# Connector-Section.net
KiCad netlist of a schematic drawn in Altium Designer
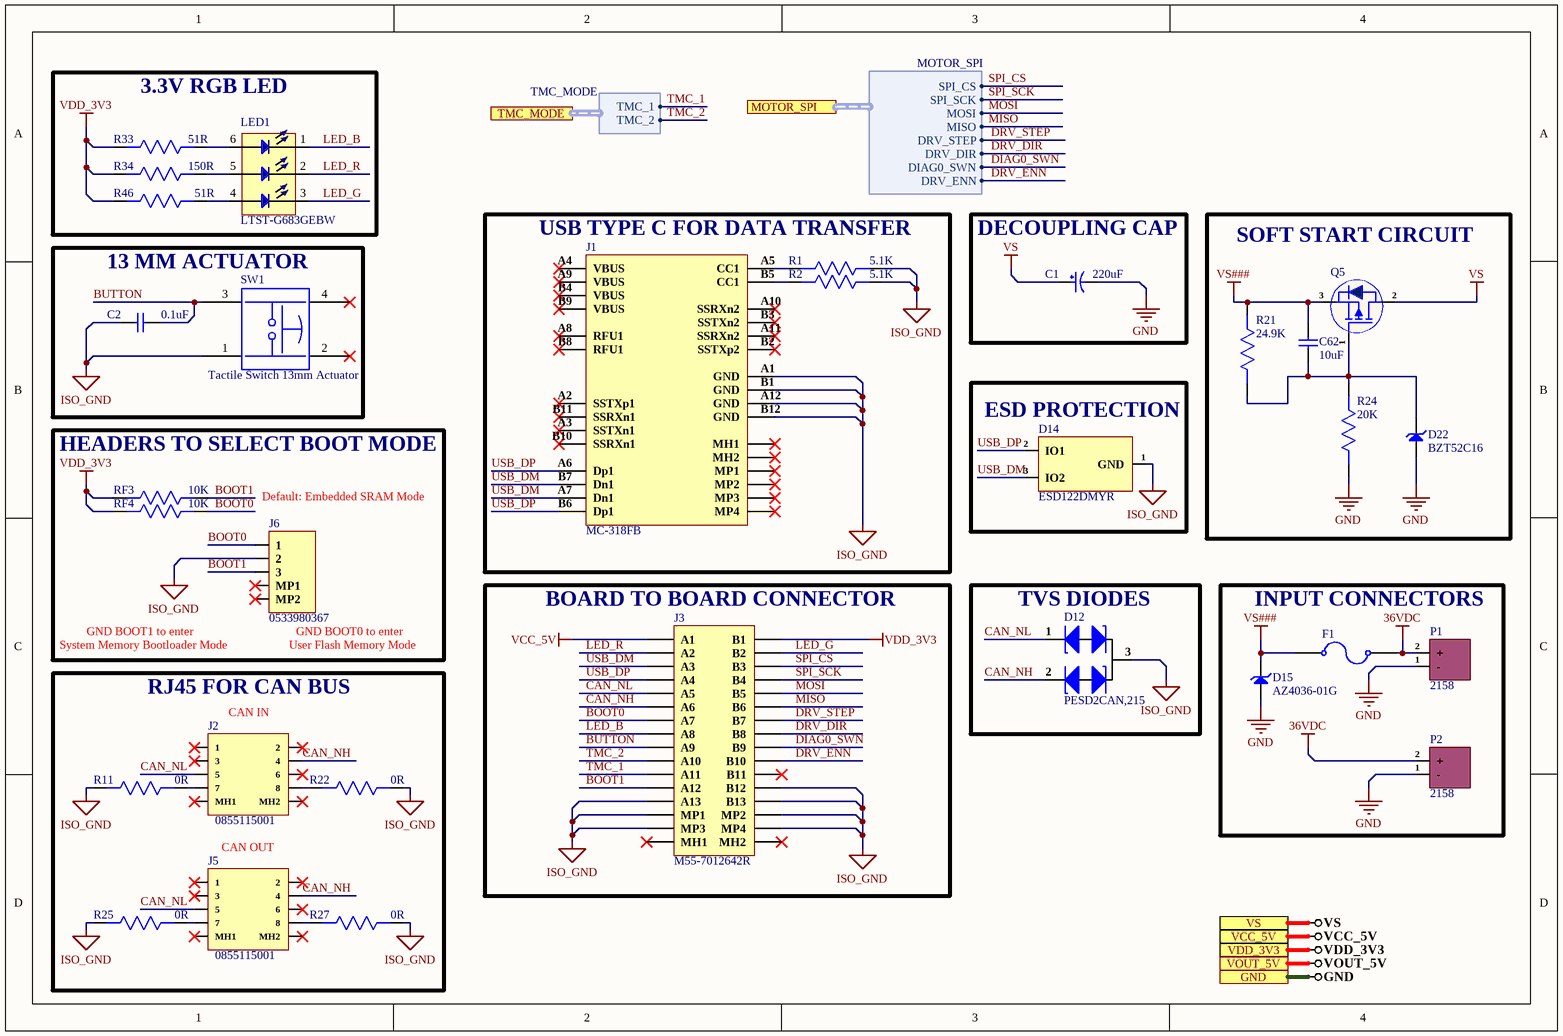
[diagram p0: Connector-Section.SchDoc]

(export (version "E")
  (design (tool "Eeschema 10.0.6"))
  (components
    (comp (ref "C1")
      (value "220uF")
      (footprint "EEEFT1H221AP")
      (description "CAP ALUM 220UF 20% 50V SMD")
      (fields
        (field (name "MANUFACTURER") "Panasonic")
        (field (name "MANUFACTURER PART NUMBER") "EEEFT1H221AP")
      )
      (libsource (lib "eSpark_centralized_Library(2022)") (part "EEEFT1H221AP"))
    )
    (comp (ref "C2")
      (value "0.1uF")
      (footprint "Cap 0603")
      (description "Cap Ceramic 0.1uF 50VDC X7R 10% SMD 0603 Paper T/R")
      (fields
        (field (name "MANUFACTURER") "Samsung")
        (field (name "MANUFACTURER PART NUMBER") "CL10B104KB8NNNC")
      )
      (libsource (lib "Cole_Benson") (part "CL10B104KB8NNNC"))
    )
    (comp (ref "C62")
      (value "10uF")
      (footprint "Cap0805")
      (description "CAP CER 10UF 50V X5R 0805")
      (fields
        (field (name "MANUFACTURER") "Samsung")
        (field (name "MANUFACTURER PART NUMBER") "CL21A106KBYQNNE")
      )
      (libsource (lib "Cole_Benson") (part "CL21A106KBYQNNE"))
    )
    (comp (ref "D12")
      (value "PESD2CAN,215")
      (footprint "SOT-23")
      (description "TVS DIODE 24VWM 41VC TO236AB")
      (fields (field (name "MANUFACTURER") "Nexperia"))
      (libsource (lib "Cole_Benson") (part "PESD2CAN,215"))
    )
    (comp (ref "D14")
      (value "ESD122DMYR")
      (footprint "X2-SON-3(0.6x1.3)")
      (description "TVS DIODE 3.6VWM 8.4VC 3X2SON")
      (fields (field (name "MANUFACTURER") "Texas Instruments") (field (name "LCSC PART NUMBER") "C1975871"))
      (libsource (lib "Cole_Benson") (part "ESD122DMYR"))
    )
    (comp (ref "D15")
      (value "AZ4036-01G")
      (footprint "SOD-123")
      (description "TVS DEVICE HIGH VOLTAGE 1-CH 36V")
      (fields (field (name "MANUFACTURER") "Amazing"))
      (libsource (lib "Cole_Benson") (part "AZ4036-01G"))
    )
    (comp (ref "D22")
      (value "BZT52C16")
      (footprint "SOD-123")
      (description "±5% Single 15.3V~17.1V 500mW 16V SOD-123 Zener Diodes ROHS")
      (fields (field (name "MANUFACTURER") "Shikues") (field (name "LCSC PART NUMBER") "C216724"))
      (libsource (lib "Cole_Benson") (part "BZT52C16"))
    )
    (comp (ref "F1")
      (value "0685P9100-01")
      (footprint "Fuse 1206 (3216 Metric)")
      (description "FUSE BOARD MOUNT 10A 50VDC 1206")
      (fields (field (name "MANUFACTURER") "Bel"))
      (libsource (lib "Cole_Benson") (part "0685P9100-01"))
    )
    (comp (ref "J1")
      (value "MC-318FB")
      (footprint "MC-318FB")
      (description "USB 3.0 3A 1 Brick nogging 24 Female -35℃~+75℃ Type-C SMD USB Connectors ROHS")
      (fields (field (name "MANUFACTURER") "SOFNG"))
      (libsource (lib "Cole_Benson") (part "MC-318FB"))
    )
    (comp (ref "J2")
      (value "0855115001")
      (footprint "0855115001")
      (description "CONN MOD JACK 8P8C VERT UNSHLD")
      (fields (field (name "MANUFACTURER") "Molex") (field (name "MANUFACTURER PART NUMBER") "85511-5001"))
      (libsource (lib "eSpark_centralized_Library(2022)") (part "0855115001"))
    )
    (comp (ref "J3")
      (value "M55-7012642R")
      (footprint "M55-7012642R")
      (description "CONN HEADER SMD 26POS 1.27MM")
      (fields (field (name "MANUFACTURER") "Harwin"))
      (libsource (lib "Cole_Benson") (part "M55-7012642R"))
    )
    (comp (ref "J5")
      (value "0855115001")
      (footprint "0855115001")
      (description "CONN MOD JACK 8P8C VERT UNSHLD")
      (fields (field (name "MANUFACTURER") "Molex") (field (name "MANUFACTURER PART NUMBER") "85511-5001"))
      (libsource (lib "eSpark_centralized_Library(2022)") (part "0855115001"))
    )
    (comp (ref "J6")
      (value "0533980367")
      (footprint "0533980367")
      (description "CONN HEADER SMD 3POS 1.25MM")
      (fields (field (name "MANUFACTURER") "Molex"))
      (libsource (lib "Cole_Benson") (part "0533980367"))
    )
    (comp (ref "LED1")
      (value "LTST-G683GEBW")
      (footprint "LTST-G683GEBW")
      (description "Standard LEDs - SMD SMD LED Red/Grn/Blue 625/1550/260 mcd")
      (fields (field (name "MANUFACTURER") "Vishay Lite-On"))
      (libsource (lib "Cole_Benson") (part "LTST-G683GEBW"))
    )
    (comp (ref "P1")
      (value "2158")
      (footprint "2158")
      (description "XT60 Connector Male-Female Pair, Black (Pololu)")
      (fields (field (name "MANUFACTURER") "Polulo"))
      (libsource (lib "Cole_Benson") (part "2158"))
    )
    (comp (ref "P2")
      (value "2158")
      (footprint "2158")
      (description "XT60 Connector Male-Female Pair, Black (Pololu)")
      (fields (field (name "MANUFACTURER") "Polulo"))
      (libsource (lib "Cole_Benson") (part "2158"))
    )
    (comp (ref "Q5")
      (value "SQD19P06-60L_GE3")
      (footprint "DPAK")
      (description "MOSFET P-CH 60V 20A TO252")
      (fields (field (name "MANUFACTURER") "Vishay") (field (name "LCSC PART NUMBER") "C143665"))
      (libsource (lib "Cole_Benson") (part "SQD19P06-60L_GE3"))
    )
    (comp (ref "R1")
      (value "5.1K")
      (footprint "Res0603")
      (description "RES SMD 5.1K OHM 5% 1/10W 0603")
      (fields
        (field (name "MANUFACTURER") "Yageo")
        (field (name "MANUFACTURER PART NUMBER") "RC0603JR-075K1L")
      )
      (libsource (lib "Cole_Benson") (part "RC0603JR-075K1L"))
    )
    (comp (ref "R2")
      (value "5.1K")
      (footprint "Res0603")
      (description "RES SMD 5.1K OHM 5% 1/10W 0603")
      (fields
        (field (name "MANUFACTURER") "Yageo")
        (field (name "MANUFACTURER PART NUMBER") "RC0603JR-075K1L")
      )
      (libsource (lib "Cole_Benson") (part "RC0603JR-075K1L"))
    )
    (comp (ref "R11")
      (value "0R")
      (footprint "Res0603")
      (description "RES SMD 0R, 1%, 0.1W, 0603")
      (fields
        (field (name "MANUFACTURER") "Yageo")
        (field (name "MANUFACTURER PART NUMBER") "RC0603FR-070RL")
      )
      (libsource (lib "Cole_Benson") (part "RC0603FR-070RL"))
    )
    (comp (ref "R21")
      (value "24.9K")
      (footprint "Res0603")
      (description "RES 24.9K OHM 1% 1/10W 0603")
      (fields
        (field (name "MANUFACTURER") "Yageo")
        (field (name "MANUFACTURER PART NUMBER") "RC0603FR-0724K9L")
      )
      (libsource (lib "Cole_Benson") (part "RC0603FR-0724K9L"))
    )
    (comp (ref "R22")
      (value "0R")
      (footprint "Res0603")
      (description "RES SMD 0R, 1%, 0.1W, 0603")
      (fields
        (field (name "MANUFACTURER") "Yageo")
        (field (name "MANUFACTURER PART NUMBER") "RC0603FR-070RL")
      )
      (libsource (lib "Cole_Benson") (part "RC0603FR-070RL"))
    )
    (comp (ref "R24")
      (value "20K")
      (footprint "Res0603")
      (description "RES 20K OHM 1% 1/10W 0603")
      (fields
        (field (name "MANUFACTURER") "Yageo")
        (field (name "MANUFACTURER PART NUMBER") "RC0603FR-0720KL")
      )
      (libsource (lib "Cole_Benson") (part "RC0603FR-0720KL"))
    )
    (comp (ref "R25")
      (value "0R")
      (footprint "Res0603")
      (description "RES SMD 0R, 1%, 0.1W, 0603")
      (fields
        (field (name "MANUFACTURER") "Yageo")
        (field (name "MANUFACTURER PART NUMBER") "RC0603FR-070RL")
      )
      (libsource (lib "Cole_Benson") (part "RC0603FR-070RL"))
    )
    (comp (ref "R27")
      (value "0R")
      (footprint "Res0603")
      (description "RES SMD 0R, 1%, 0.1W, 0603")
      (fields
        (field (name "MANUFACTURER") "Yageo")
        (field (name "MANUFACTURER PART NUMBER") "RC0603FR-070RL")
      )
      (libsource (lib "Cole_Benson") (part "RC0603FR-070RL"))
    )
    (comp (ref "R33")
      (value "51R")
      (footprint "Res0603")
      (description "RES SMD 51R 100mW 0603")
      (fields
        (field (name "MANUFACTURER") "Yageo")
        (field (name "MANUFACTURER PART NUMBER") "RC0603FR-0751RL")
      )
      (libsource (lib "Cole_Benson") (part "RC0603FR-0751RL"))
    )
    (comp (ref "R34")
      (value "150R")
      (footprint "Res0603")
      (description "RES SMD 150OHM 1/10W 0603")
      (fields
        (field (name "MANUFACTURER") "Yageo")
        (field (name "MANUFACTURER PART NUMBER") "RC0603FR-07150RL")
      )
      (libsource (lib "Cole_Benson") (part "RC0603FR-07150RL"))
    )
    (comp (ref "R46")
      (value "51R")
      (footprint "Res0603")
      (description "RES SMD 51R 100mW 0603")
      (fields
        (field (name "MANUFACTURER") "Yageo")
        (field (name "MANUFACTURER PART NUMBER") "RC0603FR-0751RL")
      )
      (libsource (lib "Cole_Benson") (part "RC0603FR-0751RL"))
    )
    (comp (ref "RF3")
      (value "10K")
      (footprint "Res0603")
      (description "RES SMD 10K Ohm 1% 1/10W 0603")
      (fields
        (field (name "MANUFACTURER") "Yageo")
        (field (name "MANUFACTURER PART NUMBER") "RC0603FR-0710KL")
      )
      (libsource (lib "Cole_Benson") (part "RC0603FR-0710KL"))
    )
    (comp (ref "RF4")
      (value "10K")
      (footprint "Res0603")
      (description "RES SMD 10K Ohm 1% 1/10W 0603")
      (fields
        (field (name "MANUFACTURER") "Yageo")
        (field (name "MANUFACTURER PART NUMBER") "RC0603FR-0710KL")
      )
      (libsource (lib "Cole_Benson") (part "RC0603FR-0710KL"))
    )
    (comp (ref "SW1")
      (value "Tactile Switch 13mm Actuator")
      (footprint "Tactile Switch 13mm Actuator")
      (description "Memontary Tactile Push Button Switch 6X6X4.3 / 4.5 / 5/6/7/8/9/10 / 13mm SMD")
      (fields
        (field (name "MANUFACTURER") "WIN ELEC-TECH CO., LTD")
        (field (name "MANUFACTURER PART NO") "Custum")
      )
      (libsource (lib "Cole_Benson") (part "Tactile Switch 13mm Actuator"))
    )
  )
  (nets
    (net (code "3") (name "/BOOT0") (class "Default")
      (node (ref "J3") (pin "A7") (pinfunction "A7_A7") (pintype "passive"))
      (node (ref "J6") (pin "1") (pinfunction "1_1") (pintype "passive"))
      (node (ref "RF4") (pin "1") (pintype "passive"))
    )
    (net (code "4") (name "/BOOT1") (class "Default")
      (node (ref "J3") (pin "A12") (pinfunction "A12_A12") (pintype "passive"))
      (node (ref "J6") (pin "3") (pinfunction "3_3") (pintype "passive"))
      (node (ref "RF3") (pin "1") (pintype "passive"))
    )
    (net (code "5") (name "/BUTTON") (class "Default")
      (node (ref "C2") (pin "2") (pinfunction "2_2") (pintype "passive"))
      (node (ref "J3") (pin "A9") (pinfunction "A9_A9") (pintype "passive"))
      (node (ref "SW1") (pin "3") (pintype "passive"))
    )
    (net (code "6") (name "/CAN_NH") (class "Default")
      (node (ref "D12") (pin "2") (pinfunction "K2_2") (pintype "passive"))
      (node (ref "J2") (pin "4") (pinfunction "4_4") (pintype "passive"))
      (node (ref "J3") (pin "A6") (pinfunction "A6_A6") (pintype "passive"))
      (node (ref "J5") (pin "4") (pinfunction "4_4") (pintype "passive"))
    )
    (net (code "7") (name "/CAN_NL") (class "Default")
      (node (ref "D12") (pin "1") (pinfunction "K1_1") (pintype "passive"))
      (node (ref "J2") (pin "5") (pinfunction "5_5") (pintype "passive"))
      (node (ref "J3") (pin "A5") (pinfunction "A5_A5") (pintype "passive"))
      (node (ref "J5") (pin "5") (pinfunction "5_5") (pintype "passive"))
    )
    (net (code "8") (name "/DIAG0_SWN") (class "Default")
      (node (ref "J3") (pin "B9") (pinfunction "B9_B9") (pintype "passive"))
    )
    (net (code "9") (name "/DRV_DIR") (class "Default")
      (node (ref "J3") (pin "B8") (pinfunction "B8_B8") (pintype "passive"))
    )
    (net (code "10") (name "/DRV_ENN") (class "Default")
      (node (ref "J3") (pin "B10") (pinfunction "B10_B10") (pintype "passive"))
    )
    (net (code "11") (name "/DRV_STEP") (class "Default")
      (node (ref "J3") (pin "B7") (pinfunction "B7_B7") (pintype "passive"))
    )
    (net (code "12") (name "/LED_B") (class "Default")
      (node (ref "J3") (pin "A8") (pinfunction "A8_A8") (pintype "passive"))
      (node (ref "LED1") (pin "1") (pinfunction "-_1") (pintype "passive"))
    )
    (net (code "13") (name "/LED_G") (class "Default")
      (node (ref "J3") (pin "B2") (pinfunction "B2_B2") (pintype "passive"))
      (node (ref "LED1") (pin "3") (pinfunction "-_3") (pintype "passive"))
    )
    (net (code "14") (name "/LED_R") (class "Default")
      (node (ref "J3") (pin "A2") (pinfunction "A2_A2") (pintype "passive"))
      (node (ref "LED1") (pin "2") (pinfunction "-_2") (pintype "passive"))
    )
    (net (code "15") (name "/MISO") (class "Default")
      (node (ref "J3") (pin "B6") (pinfunction "B6_B6") (pintype "passive"))
    )
    (net (code "16") (name "/MOSI") (class "Default")
      (node (ref "J3") (pin "B5") (pinfunction "B5_B5") (pintype "passive"))
    )
    (net (code "17") (name "/SPI_CS") (class "Default")
      (node (ref "J3") (pin "B3") (pinfunction "B3_B3") (pintype "passive"))
    )
    (net (code "18") (name "/SPI_SCK") (class "Default")
      (node (ref "J3") (pin "B4") (pinfunction "B4_B4") (pintype "passive"))
    )
    (net (code "19") (name "/TMC_1") (class "Default")
      (node (ref "J3") (pin "A11") (pinfunction "A11_A11") (pintype "passive"))
    )
    (net (code "20") (name "/TMC_2") (class "Default")
      (node (ref "J3") (pin "A10") (pinfunction "A10_A10") (pintype "passive"))
    )
    (net (code "21") (name "/USB_DM") (class "Default")
      (node (ref "D14") (pin "3") (pinfunction "IO2_3") (pintype "passive"))
      (node (ref "J1") (pin "A7") (pinfunction "Dn1_A7") (pintype "passive"))
      (node (ref "J1") (pin "B7") (pinfunction "Dn1_B7") (pintype "passive"))
      (node (ref "J3") (pin "A3") (pinfunction "A3_A3") (pintype "passive"))
    )
    (net (code "22") (name "/USB_DP") (class "Default")
      (node (ref "D14") (pin "2") (pinfunction "IO1_2") (pintype "passive"))
      (node (ref "J1") (pin "A6") (pinfunction "Dp1_A6") (pintype "passive"))
      (node (ref "J1") (pin "B6") (pinfunction "Dp1_B6") (pintype "passive"))
      (node (ref "J3") (pin "A4") (pinfunction "A4_A4") (pintype "passive"))
    )
    (net (code "25") (name "36VDC") (class "Default")
      (node (ref "F1") (pin "2") (pinfunction "2_2") (pintype "passive"))
      (node (ref "P1") (pin "2") (pinfunction "+_2") (pintype "passive"))
      (node (ref "P2") (pin "2") (pinfunction "+_2") (pintype "passive"))
    )
    (net (code "26") (name "GND") (class "Default")
      (node (ref "C1") (pin "2") (pintype "passive"))
      (node (ref "D15") (pin "2") (pinfunction "A_2") (pintype "passive"))
      (node (ref "D22") (pin "1") (pinfunction "A_1") (pintype "passive"))
      (node (ref "P1") (pin "1") (pinfunction "-_1") (pintype "passive"))
      (node (ref "P2") (pin "1") (pinfunction "-_1") (pintype "passive"))
      (node (ref "R24") (pin "2") (pintype "passive"))
    )
    (net (code "27") (name "ISO_GND") (class "Default")
      (node (ref "C2") (pin "1") (pinfunction "1_1") (pintype "passive"))
      (node (ref "D12") (pin "3") (pinfunction "C_K_3") (pintype "passive"))
      (node (ref "D14") (pin "1") (pinfunction "GND_1") (pintype "passive"))
      (node (ref "J1") (pin "A1") (pinfunction "GND_A1") (pintype "passive"))
      (node (ref "J1") (pin "A12") (pinfunction "GND_A12") (pintype "passive"))
      (node (ref "J1") (pin "B1") (pinfunction "GND_B1") (pintype "passive"))
      (node (ref "J1") (pin "B12") (pinfunction "GND_B12") (pintype "passive"))
      (node (ref "J3") (pin "A13") (pinfunction "A13_A13") (pintype "passive"))
      (node (ref "J3") (pin "B12") (pinfunction "B12_B12") (pintype "passive"))
      (node (ref "J3") (pin "B13") (pinfunction "B13_B13") (pintype "passive"))
      (node (ref "J3") (pin "MP1") (pinfunction "MP1_MP1") (pintype "passive"))
      (node (ref "J3") (pin "MP2") (pinfunction "MP2_MP2") (pintype "passive"))
      (node (ref "J3") (pin "MP3") (pinfunction "MP3_MP3") (pintype "passive"))
      (node (ref "J3") (pin "MP4") (pinfunction "MP4_MP4") (pintype "passive"))
      (node (ref "J6") (pin "2") (pinfunction "2_2") (pintype "passive"))
      (node (ref "R1") (pin "1") (pintype "passive"))
      (node (ref "R11") (pin "2") (pintype "passive"))
      (node (ref "R2") (pin "1") (pintype "passive"))
      (node (ref "R22") (pin "1") (pintype "passive"))
      (node (ref "R25") (pin "2") (pintype "passive"))
      (node (ref "R27") (pin "1") (pintype "passive"))
      (node (ref "SW1") (pin "1") (pintype "passive"))
    )
    (net (code "28") (name "Net-(D22-K)") (class "Default")
      (node (ref "C62") (pin "1") (pinfunction "1_1") (pintype "passive"))
      (node (ref "D22") (pin "2") (pinfunction "K_2") (pintype "passive"))
      (node (ref "Q5") (pin "1") (pinfunction "G_1") (pintype "passive"))
      (node (ref "R21") (pin "1") (pintype "passive"))
      (node (ref "R24") (pin "1") (pintype "passive"))
    )
    (net (code "29") (name "Net-(J1-CC1-PadA5)") (class "Default")
      (node (ref "J1") (pin "A5") (pinfunction "CC1_A5") (pintype "passive"))
      (node (ref "R1") (pin "2") (pintype "passive"))
    )
    (net (code "30") (name "Net-(J1-CC1-PadB5)") (class "Default")
      (node (ref "J1") (pin "B5") (pinfunction "CC1_B5") (pintype "passive"))
      (node (ref "R2") (pin "2") (pintype "passive"))
    )
    (net (code "31") (name "Net-(J2-Pad7)") (class "Default")
      (node (ref "J2") (pin "7") (pinfunction "7_7") (pintype "passive"))
      (node (ref "R11") (pin "1") (pintype "passive"))
    )
    (net (code "32") (name "Net-(J2-Pad8)") (class "Default")
      (node (ref "J2") (pin "8") (pinfunction "8_8") (pintype "passive"))
      (node (ref "R22") (pin "2") (pintype "passive"))
    )
    (net (code "33") (name "Net-(J5-Pad7)") (class "Default")
      (node (ref "J5") (pin "7") (pinfunction "7_7") (pintype "passive"))
      (node (ref "R25") (pin "1") (pintype "passive"))
    )
    (net (code "34") (name "Net-(J5-Pad8)") (class "Default")
      (node (ref "J5") (pin "8") (pinfunction "8_8") (pintype "passive"))
      (node (ref "R27") (pin "2") (pintype "passive"))
    )
    (net (code "35") (name "Net-(LED1-+-Pad4)") (class "Default")
      (node (ref "LED1") (pin "4") (pinfunction "+_4") (pintype "passive"))
      (node (ref "R46") (pin "1") (pintype "passive"))
    )
    (net (code "36") (name "Net-(LED1-+-Pad5)") (class "Default")
      (node (ref "LED1") (pin "5") (pinfunction "+_5") (pintype "passive"))
      (node (ref "R34") (pin "1") (pintype "passive"))
    )
    (net (code "37") (name "Net-(LED1-+-Pad6)") (class "Default")
      (node (ref "LED1") (pin "6") (pinfunction "+_6") (pintype "passive"))
      (node (ref "R33") (pin "1") (pintype "passive"))
    )
    (net (code "38") (name "VCC_5V") (class "Default")
      (node (ref "J3") (pin "A1") (pinfunction "A1_A1") (pintype "passive"))
    )
    (net (code "39") (name "VDD_3V3") (class "Default")
      (node (ref "J3") (pin "B1") (pinfunction "B1_B1") (pintype "passive"))
      (node (ref "R33") (pin "2") (pintype "passive"))
      (node (ref "R34") (pin "2") (pintype "passive"))
      (node (ref "R46") (pin "2") (pintype "passive"))
      (node (ref "RF3") (pin "2") (pintype "passive"))
      (node (ref "RF4") (pin "2") (pintype "passive"))
    )
    (net (code "41") (name "VS") (class "Default")
      (node (ref "C1") (pin "1") (pintype "passive"))
      (node (ref "Q5") (pin "2") (pinfunction "D_2") (pintype "passive"))
    )
    (net (code "42") (name "VS###") (class "Default")
      (node (ref "C62") (pin "2") (pinfunction "2_2") (pintype "passive"))
      (node (ref "D15") (pin "1") (pinfunction "K_1") (pintype "passive"))
      (node (ref "F1") (pin "1") (pinfunction "1_1") (pintype "passive"))
      (node (ref "Q5") (pin "3") (pinfunction "S_3") (pintype "passive"))
      (node (ref "R21") (pin "2") (pintype "passive"))
    )
    (net (code "43") (name "unconnected-(J1-PadMH1)") (class "Default")
      (node (ref "J1") (pin "MH1") (pinfunction "MH1_MH1") (pintype "passive+no_connect"))
    )
    (net (code "44") (name "unconnected-(J1-PadMH2)") (class "Default")
      (node (ref "J1") (pin "MH2") (pinfunction "MH2_MH2") (pintype "passive+no_connect"))
    )
    (net (code "45") (name "unconnected-(J1-PadMP1)") (class "Default")
      (node (ref "J1") (pin "MP1") (pinfunction "MP1_MP1") (pintype "passive+no_connect"))
    )
    (net (code "46") (name "unconnected-(J1-PadMP2)") (class "Default")
      (node (ref "J1") (pin "MP2") (pinfunction "MP2_MP2") (pintype "passive+no_connect"))
    )
    (net (code "47") (name "unconnected-(J1-PadMP3)") (class "Default")
      (node (ref "J1") (pin "MP3") (pinfunction "MP3_MP3") (pintype "passive+no_connect"))
    )
    (net (code "48") (name "unconnected-(J1-PadMP4)") (class "Default")
      (node (ref "J1") (pin "MP4") (pinfunction "MP4_MP4") (pintype "passive+no_connect"))
    )
    (net (code "49") (name "unconnected-(J1-RFU1-PadA8)") (class "Default")
      (node (ref "J1") (pin "A8") (pinfunction "RFU1_A8") (pintype "passive+no_connect"))
    )
    (net (code "50") (name "unconnected-(J1-RFU1-PadB8)") (class "Default")
      (node (ref "J1") (pin "B8") (pinfunction "RFU1_B8") (pintype "passive+no_connect"))
    )
    (net (code "51") (name "unconnected-(J1-SSRXn1-PadB10)") (class "Default")
      (node (ref "J1") (pin "B10") (pinfunction "SSRXn1_B10") (pintype "passive+no_connect"))
    )
    (net (code "52") (name "unconnected-(J1-SSRXn1-PadB11)") (class "Default")
      (node (ref "J1") (pin "B11") (pinfunction "SSRXn1_B11") (pintype "passive+no_connect"))
    )
    (net (code "53") (name "unconnected-(J1-SSRXn2-PadA10)") (class "Default")
      (node (ref "J1") (pin "A10") (pinfunction "SSRXn2_A10") (pintype "passive+no_connect"))
    )
    (net (code "54") (name "unconnected-(J1-SSRXn2-PadA11)") (class "Default")
      (node (ref "J1") (pin "A11") (pinfunction "SSRXn2_A11") (pintype "passive+no_connect"))
    )
    (net (code "55") (name "unconnected-(J1-SSTXn1-PadA3)") (class "Default")
      (node (ref "J1") (pin "A3") (pinfunction "SSTXn1_A3") (pintype "passive+no_connect"))
    )
    (net (code "56") (name "unconnected-(J1-SSTXn2-PadB3)") (class "Default")
      (node (ref "J1") (pin "B3") (pinfunction "SSTXn2_B3") (pintype "passive+no_connect"))
    )
    (net (code "57") (name "unconnected-(J1-SSTXp1-PadA2)") (class "Default")
      (node (ref "J1") (pin "A2") (pinfunction "SSTXp1_A2") (pintype "passive+no_connect"))
    )
    (net (code "58") (name "unconnected-(J1-SSTXp2-PadB2)") (class "Default")
      (node (ref "J1") (pin "B2") (pinfunction "SSTXp2_B2") (pintype "passive+no_connect"))
    )
    (net (code "59") (name "unconnected-(J1-VBUS-PadA4)") (class "Default")
      (node (ref "J1") (pin "A4") (pinfunction "VBUS_A4") (pintype "passive+no_connect"))
    )
    (net (code "60") (name "unconnected-(J1-VBUS-PadA9)") (class "Default")
      (node (ref "J1") (pin "A9") (pinfunction "VBUS_A9") (pintype "passive+no_connect"))
    )
    (net (code "61") (name "unconnected-(J1-VBUS-PadB4)") (class "Default")
      (node (ref "J1") (pin "B4") (pinfunction "VBUS_B4") (pintype "passive+no_connect"))
    )
    (net (code "62") (name "unconnected-(J1-VBUS-PadB9)") (class "Default")
      (node (ref "J1") (pin "B9") (pinfunction "VBUS_B9") (pintype "passive+no_connect"))
    )
    (net (code "63") (name "unconnected-(J2-Pad1)") (class "Default")
      (node (ref "J2") (pin "1") (pinfunction "1_1") (pintype "passive+no_connect"))
    )
    (net (code "64") (name "unconnected-(J2-Pad2)") (class "Default")
      (node (ref "J2") (pin "2") (pinfunction "2_2") (pintype "passive+no_connect"))
    )
    (net (code "65") (name "unconnected-(J2-Pad3)") (class "Default")
      (node (ref "J2") (pin "3") (pinfunction "3_3") (pintype "passive+no_connect"))
    )
    (net (code "66") (name "unconnected-(J2-Pad6)") (class "Default")
      (node (ref "J2") (pin "6") (pinfunction "6_6") (pintype "passive+no_connect"))
    )
    (net (code "67") (name "unconnected-(J2-PadMH1)") (class "Default")
      (node (ref "J2") (pin "MH1") (pinfunction "MH1_MH1") (pintype "passive+no_connect"))
    )
    (net (code "68") (name "unconnected-(J2-PadMH2)") (class "Default")
      (node (ref "J2") (pin "MH2") (pinfunction "MH2_MH2") (pintype "passive+no_connect"))
    )
    (net (code "69") (name "unconnected-(J3-PadB11)") (class "Default")
      (node (ref "J3") (pin "B11") (pinfunction "B11_B11") (pintype "passive+no_connect"))
    )
    (net (code "70") (name "unconnected-(J3-PadMH1)") (class "Default")
      (node (ref "J3") (pin "MH1") (pinfunction "MH1_MH1") (pintype "passive+no_connect"))
    )
    (net (code "71") (name "unconnected-(J3-PadMH2)") (class "Default")
      (node (ref "J3") (pin "MH2") (pinfunction "MH2_MH2") (pintype "passive+no_connect"))
    )
    (net (code "72") (name "unconnected-(J5-Pad1)") (class "Default")
      (node (ref "J5") (pin "1") (pinfunction "1_1") (pintype "passive+no_connect"))
    )
    (net (code "73") (name "unconnected-(J5-Pad2)") (class "Default")
      (node (ref "J5") (pin "2") (pinfunction "2_2") (pintype "passive+no_connect"))
    )
    (net (code "74") (name "unconnected-(J5-Pad3)") (class "Default")
      (node (ref "J5") (pin "3") (pinfunction "3_3") (pintype "passive+no_connect"))
    )
    (net (code "75") (name "unconnected-(J5-Pad6)") (class "Default")
      (node (ref "J5") (pin "6") (pinfunction "6_6") (pintype "passive+no_connect"))
    )
    (net (code "76") (name "unconnected-(J5-PadMH1)") (class "Default")
      (node (ref "J5") (pin "MH1") (pinfunction "MH1_MH1") (pintype "passive+no_connect"))
    )
    (net (code "77") (name "unconnected-(J5-PadMH2)") (class "Default")
      (node (ref "J5") (pin "MH2") (pinfunction "MH2_MH2") (pintype "passive+no_connect"))
    )
    (net (code "78") (name "unconnected-(J6-PadMP1)") (class "Default")
      (node (ref "J6") (pin "MP1") (pinfunction "MP1_MP1") (pintype "passive+no_connect"))
    )
    (net (code "79") (name "unconnected-(J6-PadMP2)") (class "Default")
      (node (ref "J6") (pin "MP2") (pinfunction "MP2_MP2") (pintype "passive+no_connect"))
    )
    (net (code "80") (name "unconnected-(SW1-Pad2)") (class "Default")
      (node (ref "SW1") (pin "2") (pintype "passive+no_connect"))
    )
    (net (code "81") (name "unconnected-(SW1-Pad4)") (class "Default")
      (node (ref "SW1") (pin "4") (pintype "passive+no_connect"))
    )
  )
)
